# detector.net
KiCad netlist of a schematic drawn in Altium Designer
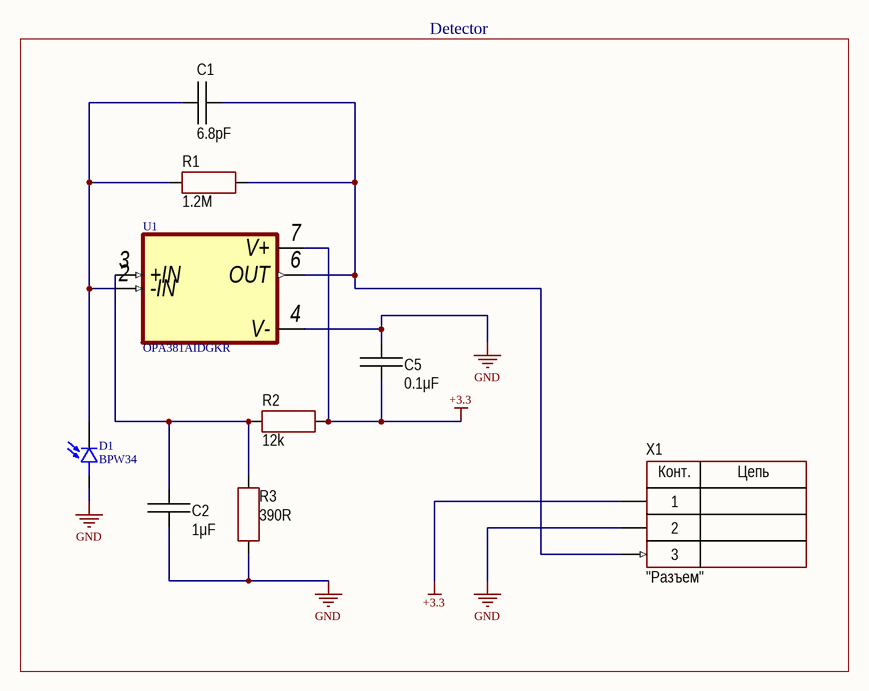
[diagram p0: detector.SchDoc]

(export (version "E")
  (design (tool "Eeschema 10.0.6"))
  (components
    (comp (ref "C1")
      (value "6.8pF")
      (footprint "CAP: 0805")
      (fields
        (field (name "MANUFACTURER") "Yageo")
        (field (name "PARTNUMBER") "CC0805KRX7R7BB104")
        (field (name "VALUEMANUFACTURERPARTNUMBER") "Ceramic capacitor, 6.8pF, X7R, ±10%, 16V, 0805, -55...+125°C")
      )
      (libsource (lib "capacitor") (part "Ceramic_0805"))
    )
    (comp (ref "C2")
      (value "1μF")
      (footprint "CAP: 0805")
      (fields
        (field (name "MANUFACTURER") "Yageo")
        (field (name "PARTNUMBER") "CC0805KRX7R7BB104")
        (field (name "VALUEMANUFACTURERPARTNUMBER") "Ceramic capacitor, 1μF, X7R, ±10%, 16V, 0805, -55...+125°C")
      )
      (libsource (lib "capacitor") (part "Ceramic_0805"))
    )
    (comp (ref "C5")
      (value "0.1μF")
      (footprint "CAP: 0805")
      (fields
        (field (name "MANUFACTURER") "Yageo")
        (field (name "PARTNUMBER") "CC0805KRX7R7BB104")
        (field (name "VALUEMANUFACTURERPARTNUMBER") "Ceramic capacitor, 0.1μF, X7R, ±10%, 16V, 0805, -55...+125°C")
      )
      (libsource (lib "capacitor") (part "Ceramic_0805"))
    )
    (comp (ref "D1")
      (value "BPW34")
      (footprint "DIO_BPW34")
      (description "Photodiode 850nm 20ns 120Â° 2-DIP (0.213, 5.40mm)")
      (fields (field (name "MF") "OSRAM Opto Semiconductors") (field (name "MP") "BPW 34"))
      (libsource (lib "BPW34") (part "BPW34"))
    )
    (comp (ref "R1")
      (value "1.2M")
      (footprint "RES: 0805")
      (fields
        (field (name "MANUFACTURER") "Yageo")
        (field (name "PARTNUMBER") "RC0805JR-07100RL")
        (field (name "VALUEMANUFACTURERPARTNUMBER") "Resistor film, 1.2M, ±5%, 0805, 0.125W, -55...+125°C")
      )
      (libsource (lib "resistor") (part "Resistor_0805"))
    )
    (comp (ref "R2")
      (value "12k")
      (footprint "RES: 0805")
      (fields
        (field (name "MANUFACTURER") "Yageo")
        (field (name "PARTNUMBER") "RC0805JR-07100RL")
        (field (name "VALUEMANUFACTURERPARTNUMBER") "Resistor film, 12k, ±5%, 0805, 0.125W, -55...+125°C")
      )
      (libsource (lib "resistor") (part "Resistor_0805"))
    )
    (comp (ref "R3")
      (value "390R")
      (footprint "RES: 0805")
      (fields
        (field (name "MANUFACTURER") "Yageo")
        (field (name "PARTNUMBER") "RC0805JR-07100RL")
        (field (name "VALUEMANUFACTURERPARTNUMBER") "Resistor film, 390R, ±5%, 0805, 0.125W, -55...+125°C")
      )
      (libsource (lib "") (part "Resistor_0805_1"))
    )
    (comp (ref "U1")
      (value "OPA381AIDGKR")
      (footprint "SOP65P490X110-8N")
      (description "Precision, Low Power, High-Speed Transimpedance Amplifier")
      (fields (field (name "MF") "Texas Instruments") (field (name "PARTNUMBER") "OPA381"))
      (libsource (lib "OPA381AIDGKR") (part "OPA381AIDGKR"))
    )
    (comp (ref "X1")
      (value "~")
      (footprint "CON: PLS-3R")
      (fields
        (field (name "MANUFACTURER") "Connfly")
        (field (name "VALUEMANUFACTURERPARTNUMBER") "Connector, 3pin, 2.54mm, 500VAC, 3A")
        (field (name "PARTNUMBER") "PLS-3R")
        (field (name "COMMENTTEXT") "\"Разъем\"")
      )
      (libsource (lib "PLS-3R") (part "PLS-3R"))
    )
  )
  (nets
    (net (code "1") (name "+3.3") (class "Default")
      (node (ref "C5") (pin "1") (pinfunction "1_1") (pintype "passive"))
      (node (ref "R2") (pin "2") (pinfunction "2_2") (pintype "passive"))
      (node (ref "U1") (pin "7") (pinfunction "V+_7") (pintype "power_in"))
      (node (ref "X1") (pin "1") (pinfunction "1_1") (pintype "power_in"))
    )
    (net (code "2") (name "GND") (class "Default")
      (node (ref "C2") (pin "1") (pinfunction "1_1") (pintype "passive"))
      (node (ref "C5") (pin "2") (pinfunction "2_2") (pintype "passive"))
      (node (ref "D1") (pin "A") (pinfunction "A_A") (pintype "passive"))
      (node (ref "R3") (pin "1") (pinfunction "1_1") (pintype "passive"))
      (node (ref "U1") (pin "4") (pinfunction "V-_4") (pintype "power_in"))
      (node (ref "X1") (pin "2") (pinfunction "2_2") (pintype "power_in"))
    )
    (net (code "3") (name "Net-(U1-+IN)") (class "Default")
      (node (ref "C2") (pin "2") (pinfunction "2_2") (pintype "passive"))
      (node (ref "R2") (pin "1") (pinfunction "1_1") (pintype "passive"))
      (node (ref "R3") (pin "2") (pinfunction "2_2") (pintype "passive"))
      (node (ref "U1") (pin "3") (pinfunction "+IN_3") (pintype "input"))
    )
    (net (code "4") (name "Net-(U1--IN)") (class "Default")
      (node (ref "C1") (pin "2") (pinfunction "2_2") (pintype "passive"))
      (node (ref "D1") (pin "C") (pinfunction "C_C") (pintype "passive"))
      (node (ref "R1") (pin "1") (pinfunction "1_1") (pintype "passive"))
      (node (ref "U1") (pin "2") (pinfunction "-IN_2") (pintype "input"))
    )
    (net (code "5") (name "Net-(U1-OUT)") (class "Default")
      (node (ref "C1") (pin "1") (pinfunction "1_1") (pintype "passive"))
      (node (ref "R1") (pin "2") (pinfunction "2_2") (pintype "passive"))
      (node (ref "U1") (pin "6") (pinfunction "OUT_6") (pintype "output"))
      (node (ref "X1") (pin "3") (pinfunction "3_3") (pintype "input"))
    )
  )
)
